# USB-interface-board.net
KiCad netlist of a schematic drawn in EAGLE
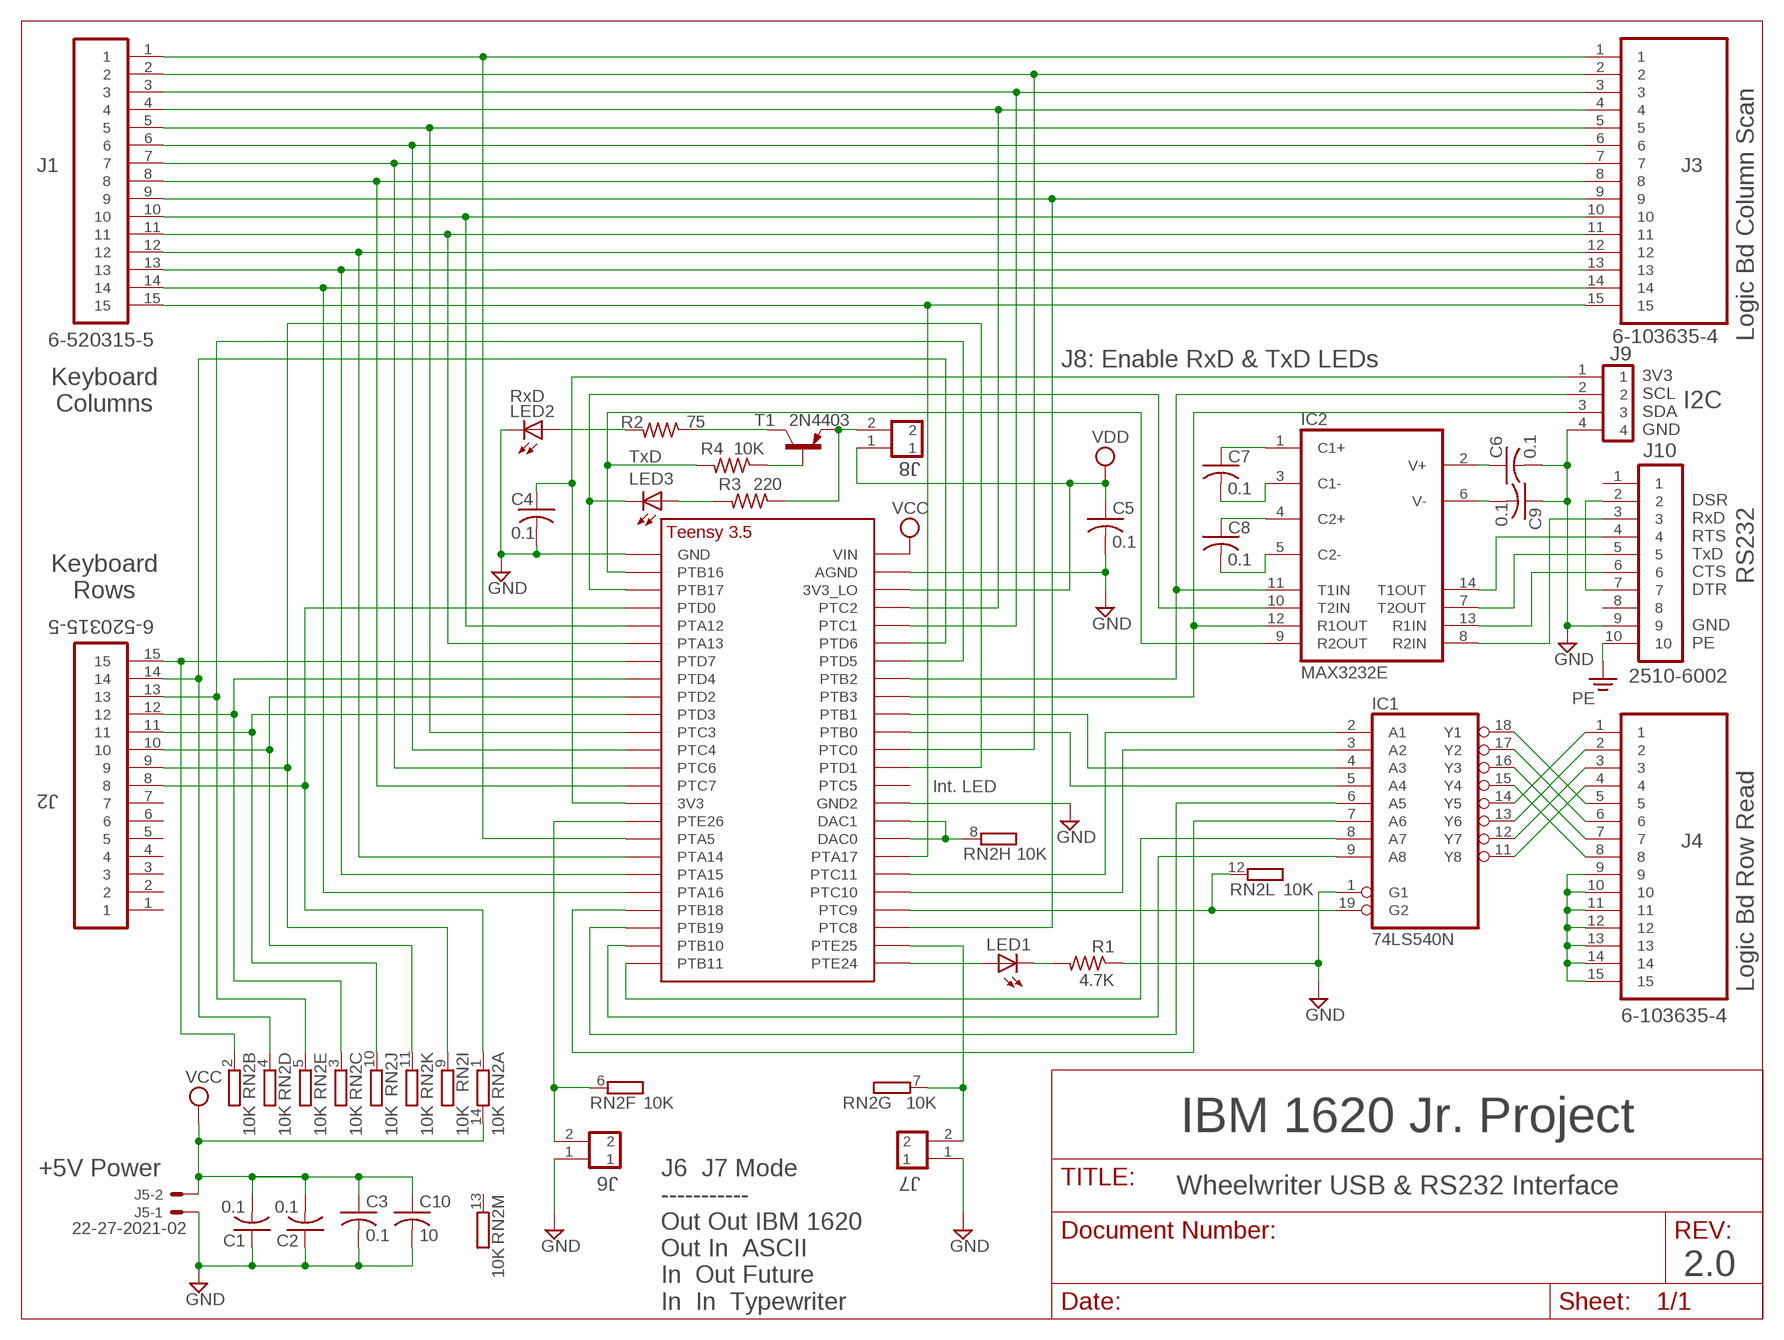
[diagram p0: schematic, sheet 1]

(export (version "E")
  (design (tool "Eeschema 10.0.6"))
  (components
    (comp (ref "C1")
      (value "0.1")
      (footprint "eagle-import:C025-025X050")
      (libsource (lib "eagle-import") (part "C-US025-025X050"))
    )
    (comp (ref "C2")
      (value "0.1")
      (footprint "eagle-import:C025-025X050")
      (libsource (lib "eagle-import") (part "C-US025-025X050"))
    )
    (comp (ref "C3")
      (value "0.1")
      (footprint "eagle-import:C025-025X050")
      (libsource (lib "eagle-import") (part "C-US025-025X050"))
    )
    (comp (ref "C4")
      (value "0.1")
      (footprint "eagle-import:C025-025X050")
      (libsource (lib "eagle-import") (part "C-US025-025X050"))
    )
    (comp (ref "C5")
      (value "0.1")
      (footprint "eagle-import:C025-025X050")
      (libsource (lib "eagle-import") (part "C-US025-025X050"))
    )
    (comp (ref "C6")
      (value "0.1")
      (footprint "eagle-import:C025-025X050")
      (libsource (lib "eagle-import") (part "C-US025-025X050"))
    )
    (comp (ref "C7")
      (value "0.1")
      (footprint "eagle-import:C025-025X050")
      (libsource (lib "eagle-import") (part "C-US025-025X050"))
    )
    (comp (ref "C8")
      (value "0.1")
      (footprint "eagle-import:C025-025X050")
      (libsource (lib "eagle-import") (part "C-US025-025X050"))
    )
    (comp (ref "C9")
      (value "0.1")
      (footprint "eagle-import:C025-025X050")
      (libsource (lib "eagle-import") (part "C-US025-025X050"))
    )
    (comp (ref "C10")
      (value "10")
      (footprint "eagle-import:C050-035X075")
      (libsource (lib "eagle-import") (part "C-US050-035X075"))
    )
    (comp (ref "IC1")
      (value "74LS540N")
      (footprint "eagle-import:DIL20")
      (libsource (lib "eagle-import") (part "74540NLS"))
    )
    (comp (ref "IC2")
      (value "MAX3232E")
      (footprint "eagle-import:DIL16")
      (fields (field (name "MPN") "MAX3232EPE+"))
      (libsource (lib "eagle-import") (part "MAX3232PEE"))
    )
    (comp (ref "J1")
      (value "6-520315-5")
      (footprint "eagle-import:6-520315-5")
      (libsource (lib "eagle-import") (part "TYCO-6-520315-5"))
    )
    (comp (ref "J2")
      (value "6-520315-5")
      (footprint "eagle-import:6-520315-5-U")
      (libsource (lib "eagle-import") (part "TYCO-6-520315-5U"))
    )
    (comp (ref "J3")
      (value "6-103635-4")
      (footprint "eagle-import:6-103635-4")
      (libsource (lib "eagle-import") (part "6-103635-4"))
    )
    (comp (ref "J4")
      (value "6-103635-4")
      (footprint "eagle-import:6-103635-4")
      (libsource (lib "eagle-import") (part "6-103635-4"))
    )
    (comp (ref "J5")
      (value "22-27-2021-02")
      (footprint "eagle-import:6410-02")
      (libsource (lib "eagle-import") (part "22-?-0227-2021"))
    )
    (comp (ref "J6")
      (value "HEADER-1X2")
      (footprint "eagle-import:HEADER-1X2")
      (fields (field (name "MPN") "BBS-102-T-A"))
      (libsource (lib "eagle-import") (part "HEADER-1X2"))
    )
    (comp (ref "J7")
      (value "HEADER-1X2")
      (footprint "eagle-import:HEADER-1X2")
      (fields (field (name "MPN") "BBS-102-T-A"))
      (libsource (lib "eagle-import") (part "HEADER-1X2"))
    )
    (comp (ref "J8")
      (value "HEADER-1X2")
      (footprint "eagle-import:HEADER-1X2")
      (fields (field (name "MPN") "BBS-102-T-A"))
      (libsource (lib "eagle-import") (part "HEADER-1X2"))
    )
    (comp (ref "J9")
      (value "HEADER-1X4")
      (footprint "eagle-import:HEADER-1X4")
      (fields (field (name "MPN") "BBS-104-T-A"))
      (libsource (lib "eagle-import") (part "HEADER-1X4"))
    )
    (comp (ref "J10")
      (value "2510-6002")
      (footprint "eagle-import:PAK100_2500-10")
      (fields (field (name "MF") "3M") (field (name "MPN") "2510-6002UB"))
      (libsource (lib "eagle-import") (part "2510-"))
    )
    (comp (ref "LED1")
      (value "LED3MM")
      (footprint "eagle-import:LED3MM")
      (libsource (lib "eagle-import") (part "LED3MM"))
    )
    (comp (ref "LED2")
      (value "RxD")
      (footprint "eagle-import:LED3MM")
      (libsource (lib "eagle-import") (part "LED3MM"))
    )
    (comp (ref "LED3")
      (value "TxD")
      (footprint "eagle-import:LED3MM")
      (libsource (lib "eagle-import") (part "LED3MM"))
    )
    (comp (ref "R1")
      (value "4.7K")
      (footprint "eagle-import:0204_5")
      (libsource (lib "eagle-import") (part "R-US_0204/5"))
    )
    (comp (ref "R2")
      (value "75")
      (footprint "eagle-import:0204_5")
      (libsource (lib "eagle-import") (part "R-US_0204/5"))
    )
    (comp (ref "R3")
      (value "220")
      (footprint "eagle-import:0204_5")
      (libsource (lib "eagle-import") (part "R-US_0204/5"))
    )
    (comp (ref "R4")
      (value "10K")
      (footprint "eagle-import:0204_5")
      (libsource (lib "eagle-import") (part "R-US_0204/5"))
    )
    (comp (ref "RN2")
      (value "10K")
      (footprint "eagle-import:DIL14")
      (libsource (lib "eagle-import") (part "E13R"))
    )
    (comp (ref "T1")
      (value "2N4403")
      (footprint "eagle-import:TO92")
      (libsource (lib "eagle-import") (part "2N3906"))
    )
    (comp (ref "U$1")
      (value "TEENSY_3.5_BASIC")
      (footprint "eagle-import:TEENSY_3.5_BASIC")
      (libsource (lib "eagle-import") (part "TEENSY_3.5_BASIC"))
    )
  )
  (nets
    (net (code "1") (name "GND") (class "Default")
      (node (ref "C1") (pin "1") (pinfunction "1_1") (pintype "passive"))
      (node (ref "C10") (pin "2") (pinfunction "2_2") (pintype "passive"))
      (node (ref "C2") (pin "1") (pinfunction "1_1") (pintype "passive"))
      (node (ref "C3") (pin "2") (pinfunction "2_2") (pintype "passive"))
      (node (ref "C4") (pin "2") (pinfunction "2_2") (pintype "passive"))
      (node (ref "C5") (pin "2") (pinfunction "2_2") (pintype "passive"))
      (node (ref "C6") (pin "2") (pinfunction "2_2") (pintype "passive"))
      (node (ref "C9") (pin "1") (pinfunction "1_1") (pintype "passive"))
      (node (ref "IC1") (pin "1") (pinfunction "G1_1") (pintype "input"))
      (node (ref "J10") (pin "9") (pinfunction "9_9") (pintype "passive"))
      (node (ref "J5") (pin "1") (pinfunction "S_1") (pintype "passive"))
      (node (ref "J6") (pin "1") (pinfunction "1_1") (pintype "passive"))
      (node (ref "J7") (pin "1") (pinfunction "1_1") (pintype "passive"))
      (node (ref "J9") (pin "4") (pinfunction "4_4") (pintype "passive"))
      (node (ref "LED2") (pin "K") (pinfunction "C_K") (pintype "passive"))
      (node (ref "R1") (pin "1") (pinfunction "1_1") (pintype "passive"))
      (node (ref "U$1") (pin "AGND") (pinfunction "AGND_AGND") (pintype "bidirectional"))
      (node (ref "U$1") (pin "GND") (pinfunction "GND_GND") (pintype "bidirectional"))
      (node (ref "U$1") (pin "GND2") (pinfunction "GND2_GND2") (pintype "bidirectional"))
    )
    (net (code "2") (name "Net-(C4-Pad1)") (class "Default")
      (node (ref "C4") (pin "1") (pinfunction "1_1") (pintype "passive"))
      (node (ref "J9") (pin "1") (pinfunction "1_1") (pintype "passive"))
      (node (ref "U$1") (pin "3V3") (pinfunction "3V3_3V3") (pintype "bidirectional"))
    )
    (net (code "3") (name "Net-(IC1A-A1)") (class "Default")
      (node (ref "IC1") (pin "2") (pinfunction "A1_2") (pintype "input"))
      (node (ref "U$1") (pin "PTC11") (pinfunction "PTC11_PTC11") (pintype "bidirectional"))
    )
    (net (code "4") (name "Net-(IC1A-A2)") (class "Default")
      (node (ref "IC1") (pin "3") (pinfunction "A2_3") (pintype "input"))
      (node (ref "U$1") (pin "PTC10") (pinfunction "PTC10_PTC10") (pintype "bidirectional"))
    )
    (net (code "5") (name "Net-(IC1A-A3)") (class "Default")
      (node (ref "IC1") (pin "4") (pinfunction "A3_4") (pintype "input"))
      (node (ref "U$1") (pin "PTB1") (pinfunction "PTB1_PTB1") (pintype "bidirectional"))
    )
    (net (code "6") (name "Net-(IC1A-A4)") (class "Default")
      (node (ref "IC1") (pin "5") (pinfunction "A4_5") (pintype "input"))
      (node (ref "U$1") (pin "PTB0") (pinfunction "PTB0_PTB0") (pintype "bidirectional"))
    )
    (net (code "7") (name "Net-(IC1A-A5)") (class "Default")
      (node (ref "IC1") (pin "6") (pinfunction "A5_6") (pintype "input"))
      (node (ref "U$1") (pin "PTB19") (pinfunction "PTB19_PTB19") (pintype "bidirectional"))
    )
    (net (code "8") (name "Net-(IC1A-A6)") (class "Default")
      (node (ref "IC1") (pin "7") (pinfunction "A6_7") (pintype "input"))
      (node (ref "U$1") (pin "PTB18") (pinfunction "PTB18_PTB18") (pintype "bidirectional"))
    )
    (net (code "9") (name "Net-(IC1A-A7)") (class "Default")
      (node (ref "IC1") (pin "8") (pinfunction "A7_8") (pintype "input"))
      (node (ref "U$1") (pin "PTB11") (pinfunction "PTB11_PTB11") (pintype "bidirectional"))
    )
    (net (code "10") (name "Net-(IC1A-A8)") (class "Default")
      (node (ref "IC1") (pin "9") (pinfunction "A8_9") (pintype "input"))
      (node (ref "U$1") (pin "PTB10") (pinfunction "PTB10_PTB10") (pintype "bidirectional"))
    )
    (net (code "11") (name "Net-(IC1A-G2)") (class "Default")
      (node (ref "IC1") (pin "19") (pinfunction "G2_19") (pintype "input"))
      (node (ref "RN2") (pin "12") (pinfunction "1_12") (pintype "passive"))
      (node (ref "U$1") (pin "PTC9") (pinfunction "PTC9_PTC9") (pintype "bidirectional"))
    )
    (net (code "12") (name "Net-(IC1A-Y1)") (class "Default")
      (node (ref "IC1") (pin "18") (pinfunction "Y1_18") (pintype "tri_state"))
      (node (ref "J4") (pin "5") (pinfunction "5_5") (pintype "passive"))
    )
    (net (code "13") (name "Net-(IC1A-Y2)") (class "Default")
      (node (ref "IC1") (pin "17") (pinfunction "Y2_17") (pintype "tri_state"))
      (node (ref "J4") (pin "6") (pinfunction "6_6") (pintype "passive"))
    )
    (net (code "14") (name "Net-(IC1A-Y3)") (class "Default")
      (node (ref "IC1") (pin "16") (pinfunction "Y3_16") (pintype "tri_state"))
      (node (ref "J4") (pin "7") (pinfunction "7_7") (pintype "passive"))
    )
    (net (code "15") (name "Net-(IC1A-Y4)") (class "Default")
      (node (ref "IC1") (pin "15") (pinfunction "Y4_15") (pintype "tri_state"))
      (node (ref "J4") (pin "8") (pinfunction "8_8") (pintype "passive"))
    )
    (net (code "16") (name "Net-(IC1A-Y5)") (class "Default")
      (node (ref "IC1") (pin "14") (pinfunction "Y5_14") (pintype "tri_state"))
      (node (ref "J4") (pin "1") (pinfunction "1_1") (pintype "passive"))
    )
    (net (code "17") (name "Net-(IC1A-Y6)") (class "Default")
      (node (ref "IC1") (pin "13") (pinfunction "Y6_13") (pintype "tri_state"))
      (node (ref "J4") (pin "2") (pinfunction "2_2") (pintype "passive"))
    )
    (net (code "18") (name "Net-(IC1A-Y7)") (class "Default")
      (node (ref "IC1") (pin "12") (pinfunction "Y7_12") (pintype "tri_state"))
      (node (ref "J4") (pin "3") (pinfunction "3_3") (pintype "passive"))
    )
    (net (code "19") (name "Net-(IC1A-Y8)") (class "Default")
      (node (ref "IC1") (pin "11") (pinfunction "Y8_11") (pintype "tri_state"))
      (node (ref "J4") (pin "4") (pinfunction "4_4") (pintype "passive"))
    )
    (net (code "20") (name "Net-(IC2A-C1+)") (class "Default")
      (node (ref "C7") (pin "1") (pinfunction "1_1") (pintype "passive"))
      (node (ref "IC2") (pin "1") (pinfunction "C1+_1") (pintype "bidirectional"))
    )
    (net (code "21") (name "Net-(IC2A-C1-)") (class "Default")
      (node (ref "C7") (pin "2") (pinfunction "2_2") (pintype "passive"))
      (node (ref "IC2") (pin "3") (pinfunction "C1-_3") (pintype "bidirectional"))
    )
    (net (code "22") (name "Net-(IC2A-C2+)") (class "Default")
      (node (ref "C8") (pin "1") (pinfunction "1_1") (pintype "passive"))
      (node (ref "IC2") (pin "4") (pinfunction "C2+_4") (pintype "bidirectional"))
    )
    (net (code "23") (name "Net-(IC2A-C2-)") (class "Default")
      (node (ref "C8") (pin "2") (pinfunction "2_2") (pintype "passive"))
      (node (ref "IC2") (pin "5") (pinfunction "C2-_5") (pintype "bidirectional"))
    )
    (net (code "24") (name "Net-(IC2A-R1IN)") (class "Default")
      (node (ref "IC2") (pin "13") (pinfunction "R1IN_13") (pintype "input"))
      (node (ref "J10") (pin "6") (pinfunction "6_6") (pintype "passive"))
    )
    (net (code "25") (name "Net-(IC2A-R1OUT)") (class "Default")
      (node (ref "IC2") (pin "12") (pinfunction "R1OUT_12") (pintype "output"))
      (node (ref "J9") (pin "3") (pinfunction "3_3") (pintype "passive"))
      (node (ref "U$1") (pin "PTB3") (pinfunction "PTB3_PTB3") (pintype "bidirectional"))
    )
    (net (code "26") (name "Net-(IC2A-R2IN)") (class "Default")
      (node (ref "IC2") (pin "8") (pinfunction "R2IN_8") (pintype "input"))
      (node (ref "J10") (pin "3") (pinfunction "3_3") (pintype "passive"))
    )
    (net (code "27") (name "Net-(IC2A-R2OUT)") (class "Default")
      (node (ref "IC2") (pin "9") (pinfunction "R2OUT_9") (pintype "output"))
      (node (ref "R4") (pin "2") (pinfunction "2_2") (pintype "passive"))
      (node (ref "U$1") (pin "PTB16") (pinfunction "PTB16_PTB16") (pintype "bidirectional"))
    )
    (net (code "28") (name "Net-(IC2A-T1IN)") (class "Default")
      (node (ref "IC2") (pin "11") (pinfunction "T1IN_11") (pintype "input"))
      (node (ref "J9") (pin "2") (pinfunction "2_2") (pintype "passive"))
      (node (ref "U$1") (pin "PTB2") (pinfunction "PTB2_PTB2") (pintype "bidirectional"))
    )
    (net (code "29") (name "Net-(IC2A-T1OUT)") (class "Default")
      (node (ref "IC2") (pin "14") (pinfunction "T1OUT_14") (pintype "output"))
      (node (ref "J10") (pin "4") (pinfunction "4_4") (pintype "passive"))
    )
    (net (code "30") (name "Net-(IC2A-T2IN)") (class "Default")
      (node (ref "IC2") (pin "10") (pinfunction "T2IN_10") (pintype "input"))
      (node (ref "LED3") (pin "K") (pinfunction "C_K") (pintype "passive"))
      (node (ref "U$1") (pin "PTB17") (pinfunction "PTB17_PTB17") (pintype "bidirectional"))
    )
    (net (code "31") (name "Net-(IC2A-T2OUT)") (class "Default")
      (node (ref "IC2") (pin "7") (pinfunction "T2OUT_7") (pintype "output"))
      (node (ref "J10") (pin "5") (pinfunction "5_5") (pintype "passive"))
    )
    (net (code "32") (name "Net-(IC2A-V+)") (class "Default")
      (node (ref "C6") (pin "1") (pinfunction "1_1") (pintype "passive"))
      (node (ref "IC2") (pin "2") (pinfunction "V+_2") (pintype "bidirectional"))
    )
    (net (code "33") (name "Net-(IC2A-V-)") (class "Default")
      (node (ref "C9") (pin "2") (pinfunction "2_2") (pintype "passive"))
      (node (ref "IC2") (pin "6") (pinfunction "V-_6") (pintype "bidirectional"))
    )
    (net (code "34") (name "Net-(J1-Pad1)") (class "Default")
      (node (ref "J1") (pin "1") (pinfunction "1_1") (pintype "passive"))
      (node (ref "J3") (pin "1") (pinfunction "1_1") (pintype "passive"))
      (node (ref "U$1") (pin "PTA5") (pinfunction "PTA5_PTA5") (pintype "bidirectional"))
    )
    (net (code "35") (name "Net-(J1-Pad2)") (class "Default")
      (node (ref "J1") (pin "2") (pinfunction "2_2") (pintype "passive"))
      (node (ref "J3") (pin "2") (pinfunction "2_2") (pintype "passive"))
      (node (ref "U$1") (pin "PTC0") (pinfunction "PTC0_PTC0") (pintype "bidirectional"))
    )
    (net (code "36") (name "Net-(J1-Pad3)") (class "Default")
      (node (ref "J1") (pin "3") (pinfunction "3_3") (pintype "passive"))
      (node (ref "J3") (pin "3") (pinfunction "3_3") (pintype "passive"))
      (node (ref "U$1") (pin "PTC1") (pinfunction "PTC1_PTC1") (pintype "bidirectional"))
    )
    (net (code "37") (name "Net-(J1-Pad4)") (class "Default")
      (node (ref "J1") (pin "4") (pinfunction "4_4") (pintype "passive"))
      (node (ref "J3") (pin "4") (pinfunction "4_4") (pintype "passive"))
      (node (ref "U$1") (pin "PTC2") (pinfunction "PTC2_PTC2") (pintype "bidirectional"))
    )
    (net (code "38") (name "Net-(J1-Pad5)") (class "Default")
      (node (ref "J1") (pin "5") (pinfunction "5_5") (pintype "passive"))
      (node (ref "J3") (pin "5") (pinfunction "5_5") (pintype "passive"))
      (node (ref "U$1") (pin "PTC3") (pinfunction "PTC3_PTC3") (pintype "bidirectional"))
    )
    (net (code "39") (name "Net-(J1-Pad6)") (class "Default")
      (node (ref "J1") (pin "6") (pinfunction "6_6") (pintype "passive"))
      (node (ref "J3") (pin "6") (pinfunction "6_6") (pintype "passive"))
      (node (ref "U$1") (pin "PTC4") (pinfunction "PTC4_PTC4") (pintype "bidirectional"))
    )
    (net (code "40") (name "Net-(J1-Pad7)") (class "Default")
      (node (ref "J1") (pin "7") (pinfunction "7_7") (pintype "passive"))
      (node (ref "J3") (pin "7") (pinfunction "7_7") (pintype "passive"))
      (node (ref "U$1") (pin "PTC6") (pinfunction "PTC6_PTC6") (pintype "bidirectional"))
    )
    (net (code "41") (name "Net-(J1-Pad8)") (class "Default")
      (node (ref "J1") (pin "8") (pinfunction "8_8") (pintype "passive"))
      (node (ref "J3") (pin "8") (pinfunction "8_8") (pintype "passive"))
      (node (ref "U$1") (pin "PTC7") (pinfunction "PTC7_PTC7") (pintype "bidirectional"))
    )
    (net (code "42") (name "Net-(J1-Pad9)") (class "Default")
      (node (ref "J1") (pin "9") (pinfunction "9_9") (pintype "passive"))
      (node (ref "J3") (pin "9") (pinfunction "9_9") (pintype "passive"))
      (node (ref "U$1") (pin "PTC8") (pinfunction "PTC8_PTC8") (pintype "bidirectional"))
    )
    (net (code "43") (name "Net-(J1-Pad10)") (class "Default")
      (node (ref "J1") (pin "10") (pinfunction "10_10") (pintype "passive"))
      (node (ref "J3") (pin "10") (pinfunction "10_10") (pintype "passive"))
      (node (ref "U$1") (pin "PTA12") (pinfunction "PTA12_PTA12") (pintype "bidirectional"))
    )
    (net (code "44") (name "Net-(J1-Pad11)") (class "Default")
      (node (ref "J1") (pin "11") (pinfunction "11_11") (pintype "passive"))
      (node (ref "J3") (pin "11") (pinfunction "11_11") (pintype "passive"))
      (node (ref "U$1") (pin "PTA13") (pinfunction "PTA13_PTA13") (pintype "bidirectional"))
    )
    (net (code "45") (name "Net-(J1-Pad12)") (class "Default")
      (node (ref "J1") (pin "12") (pinfunction "12_12") (pintype "passive"))
      (node (ref "J3") (pin "12") (pinfunction "12_12") (pintype "passive"))
      (node (ref "U$1") (pin "PTA14") (pinfunction "PTA14_PTA14") (pintype "bidirectional"))
    )
    (net (code "46") (name "Net-(J1-Pad13)") (class "Default")
      (node (ref "J1") (pin "13") (pinfunction "13_13") (pintype "passive"))
      (node (ref "J3") (pin "13") (pinfunction "13_13") (pintype "passive"))
      (node (ref "U$1") (pin "PTA15") (pinfunction "PTA15_PTA15") (pintype "bidirectional"))
    )
    (net (code "47") (name "Net-(J1-Pad14)") (class "Default")
      (node (ref "J1") (pin "14") (pinfunction "14_14") (pintype "passive"))
      (node (ref "J3") (pin "14") (pinfunction "14_14") (pintype "passive"))
      (node (ref "U$1") (pin "PTA16") (pinfunction "PTA16_PTA16") (pintype "bidirectional"))
    )
    (net (code "48") (name "Net-(J1-Pad15)") (class "Default")
      (node (ref "J1") (pin "15") (pinfunction "15_15") (pintype "passive"))
      (node (ref "J3") (pin "15") (pinfunction "15_15") (pintype "passive"))
      (node (ref "U$1") (pin "PTA17") (pinfunction "PTA17_PTA17") (pintype "bidirectional"))
    )
    (net (code "49") (name "Net-(J2-Pad8)") (class "Default")
      (node (ref "J2") (pin "8") (pinfunction "8_8") (pintype "passive"))
      (node (ref "RN2") (pin "1") (pinfunction "1_1") (pintype "passive"))
      (node (ref "U$1") (pin "PTD0") (pinfunction "PTD0_PTD0") (pintype "bidirectional"))
    )
    (net (code "50") (name "Net-(J4-Pad10)") (class "Default")
      (node (ref "J4") (pin "10") (pinfunction "10_10") (pintype "passive"))
      (node (ref "J4") (pin "11") (pinfunction "11_11") (pintype "passive"))
      (node (ref "J4") (pin "12") (pinfunction "12_12") (pintype "passive"))
      (node (ref "J4") (pin "13") (pinfunction "13_13") (pintype "passive"))
      (node (ref "J4") (pin "14") (pinfunction "14_14") (pintype "passive"))
      (node (ref "J4") (pin "15") (pinfunction "15_15") (pintype "passive"))
      (node (ref "J4") (pin "9") (pinfunction "9_9") (pintype "passive"))
    )
    (net (code "51") (name "Net-(J10-Pad2)") (class "Default")
      (node (ref "J10") (pin "2") (pinfunction "2_2") (pintype "passive"))
      (node (ref "J10") (pin "7") (pinfunction "7_7") (pintype "passive"))
    )
    (net (code "52") (name "Net-(LED1-C)") (class "Default")
      (node (ref "LED1") (pin "K") (pinfunction "C_K") (pintype "passive"))
      (node (ref "R1") (pin "2") (pinfunction "2_2") (pintype "passive"))
    )
    (net (code "53") (name "Net-(LED1-PadA)") (class "Default")
      (node (ref "LED1") (pin "A") (pinfunction "A_A") (pintype "passive"))
      (node (ref "U$1") (pin "PTE24") (pinfunction "PTE24_PTE24") (pintype "bidirectional"))
    )
    (net (code "54") (name "Net-(LED2-PadA)") (class "Default")
      (node (ref "LED2") (pin "A") (pinfunction "A_A") (pintype "passive"))
      (node (ref "R2") (pin "2") (pinfunction "2_2") (pintype "passive"))
    )
    (net (code "55") (name "Net-(LED3-PadA)") (class "Default")
      (node (ref "LED3") (pin "A") (pinfunction "A_A") (pintype "passive"))
      (node (ref "R3") (pin "2") (pinfunction "2_2") (pintype "passive"))
    )
    (net (code "56") (name "Net-(RN2B-1)") (class "Default")
      (node (ref "J2") (pin "15") (pinfunction "15_15") (pintype "passive"))
      (node (ref "RN2") (pin "2") (pinfunction "1_2") (pintype "passive"))
      (node (ref "U$1") (pin "PTD7") (pinfunction "PTD7_PTD7") (pintype "bidirectional"))
    )
    (net (code "57") (name "Net-(RN2C-1)") (class "Default")
      (node (ref "J2") (pin "12") (pinfunction "12_12") (pintype "passive"))
      (node (ref "RN2") (pin "3") (pinfunction "1_3") (pintype "passive"))
      (node (ref "U$1") (pin "PTD4") (pinfunction "PTD4_PTD4") (pintype "bidirectional"))
    )
    (net (code "58") (name "Net-(RN2D-1)") (class "Default")
      (node (ref "J2") (pin "14") (pinfunction "14_14") (pintype "passive"))
      (node (ref "RN2") (pin "4") (pinfunction "1_4") (pintype "passive"))
      (node (ref "U$1") (pin "PTD6") (pinfunction "PTD6_PTD6") (pintype "bidirectional"))
    )
    (net (code "59") (name "Net-(RN2E-1)") (class "Default")
      (node (ref "J2") (pin "13") (pinfunction "13_13") (pintype "passive"))
      (node (ref "RN2") (pin "5") (pinfunction "1_5") (pintype "passive"))
      (node (ref "U$1") (pin "PTD5") (pinfunction "PTD5_PTD5") (pintype "bidirectional"))
    )
    (net (code "60") (name "Net-(RN2F-1)") (class "Default")
      (node (ref "J6") (pin "2") (pinfunction "2_2") (pintype "passive"))
      (node (ref "RN2") (pin "6") (pinfunction "1_6") (pintype "passive"))
      (node (ref "U$1") (pin "PTE26") (pinfunction "PTE26_PTE26") (pintype "bidirectional"))
    )
    (net (code "61") (name "Net-(RN2G-1)") (class "Default")
      (node (ref "J7") (pin "2") (pinfunction "2_2") (pintype "passive"))
      (node (ref "RN2") (pin "7") (pinfunction "1_7") (pintype "passive"))
      (node (ref "U$1") (pin "PTE25") (pinfunction "PTE25_PTE25") (pintype "bidirectional"))
    )
    (net (code "62") (name "Net-(RN2H-1)") (class "Default")
      (node (ref "RN2") (pin "8") (pinfunction "1_8") (pintype "passive"))
      (node (ref "U$1") (pin "DAC0") (pinfunction "DAC0_DAC0") (pintype "bidirectional"))
      (node (ref "U$1") (pin "DAC1") (pinfunction "DAC1_DAC1") (pintype "bidirectional"))
    )
    (net (code "63") (name "Net-(RN2I-1)") (class "Default")
      (node (ref "J2") (pin "9") (pinfunction "9_9") (pintype "passive"))
      (node (ref "RN2") (pin "9") (pinfunction "1_9") (pintype "passive"))
      (node (ref "U$1") (pin "PTD1") (pinfunction "PTD1_PTD1") (pintype "bidirectional"))
    )
    (net (code "64") (name "Net-(RN2J-1)") (class "Default")
      (node (ref "J2") (pin "11") (pinfunction "11_11") (pintype "passive"))
      (node (ref "RN2") (pin "10") (pinfunction "1_10") (pintype "passive"))
      (node (ref "U$1") (pin "PTD3") (pinfunction "PTD3_PTD3") (pintype "bidirectional"))
    )
    (net (code "65") (name "Net-(RN2K-1)") (class "Default")
      (node (ref "J2") (pin "10") (pinfunction "10_10") (pintype "passive"))
      (node (ref "RN2") (pin "11") (pinfunction "1_11") (pintype "passive"))
      (node (ref "U$1") (pin "PTD2") (pinfunction "PTD2_PTD2") (pintype "bidirectional"))
    )
    (net (code "66") (name "Net-(T1-B)") (class "Default")
      (node (ref "R4") (pin "1") (pinfunction "1_1") (pintype "passive"))
      (node (ref "T1") (pin "2") (pinfunction "B_2") (pintype "passive"))
    )
    (net (code "67") (name "Net-(T1-C)") (class "Default")
      (node (ref "R2") (pin "1") (pinfunction "1_1") (pintype "passive"))
      (node (ref "T1") (pin "1") (pinfunction "C_1") (pintype "passive"))
    )
    (net (code "68") (name "Net-(T1-E)") (class "Default")
      (node (ref "J8") (pin "2") (pinfunction "2_2") (pintype "passive"))
      (node (ref "R3") (pin "1") (pinfunction "1_1") (pintype "passive"))
      (node (ref "T1") (pin "3") (pinfunction "E_3") (pintype "passive"))
    )
    (net (code "69") (name "PE") (class "Default")
      (node (ref "J10") (pin "10") (pinfunction "10_10") (pintype "passive"))
    )
    (net (code "70") (name "VCC") (class "Default")
      (node (ref "C1") (pin "2") (pinfunction "2_2") (pintype "passive"))
      (node (ref "C10") (pin "1") (pinfunction "1_1") (pintype "passive"))
      (node (ref "C2") (pin "2") (pinfunction "2_2") (pintype "passive"))
      (node (ref "C3") (pin "1") (pinfunction "1_1") (pintype "passive"))
      (node (ref "J5") (pin "2") (pinfunction "S_2") (pintype "passive"))
      (node (ref "RN2") (pin "14") (pinfunction "2_14") (pintype "passive"))
      (node (ref "U$1") (pin "VIN") (pinfunction "VIN_VIN") (pintype "bidirectional"))
    )
    (net (code "71") (name "VDD") (class "Default")
      (node (ref "C5") (pin "1") (pinfunction "1_1") (pintype "passive"))
      (node (ref "J8") (pin "1") (pinfunction "1_1") (pintype "passive"))
      (node (ref "U$1") (pin "3V3_LO") (pinfunction "3V3_LO_3V3_LO") (pintype "bidirectional"))
    )
    (net (code "72") (name "unconnected-(J2-Pad1)") (class "Default")
      (node (ref "J2") (pin "1") (pinfunction "1_1") (pintype "passive"))
    )
    (net (code "73") (name "unconnected-(J2-Pad2)") (class "Default")
      (node (ref "J2") (pin "2") (pinfunction "2_2") (pintype "passive"))
    )
    (net (code "74") (name "unconnected-(J2-Pad3)") (class "Default")
      (node (ref "J2") (pin "3") (pinfunction "3_3") (pintype "passive"))
    )
    (net (code "75") (name "unconnected-(J2-Pad4)") (class "Default")
      (node (ref "J2") (pin "4") (pinfunction "4_4") (pintype "passive"))
    )
    (net (code "76") (name "unconnected-(J2-Pad5)") (class "Default")
      (node (ref "J2") (pin "5") (pinfunction "5_5") (pintype "passive"))
    )
    (net (code "77") (name "unconnected-(J2-Pad6)") (class "Default")
      (node (ref "J2") (pin "6") (pinfunction "6_6") (pintype "passive"))
    )
    (net (code "78") (name "unconnected-(J2-Pad7)") (class "Default")
      (node (ref "J2") (pin "7") (pinfunction "7_7") (pintype "passive"))
    )
    (net (code "79") (name "unconnected-(J10-Pad1)") (class "Default")
      (node (ref "J10") (pin "1") (pinfunction "1_1") (pintype "passive"))
    )
    (net (code "80") (name "unconnected-(J10-Pad8)") (class "Default")
      (node (ref "J10") (pin "8") (pinfunction "8_8") (pintype "passive"))
    )
    (net (code "81") (name "unconnected-(RN2M-1-Pad13)") (class "Default")
      (node (ref "RN2") (pin "13") (pinfunction "1_13") (pintype "passive"))
    )
    (net (code "82") (name "unconnected-(U$1-PadPTC5)") (class "Default")
      (node (ref "U$1") (pin "PTC5") (pinfunction "PTC5_PTC5") (pintype "bidirectional"))
    )
  )
)
